# Alimentations.net
KiCad netlist of a schematic drawn in Altium Designer
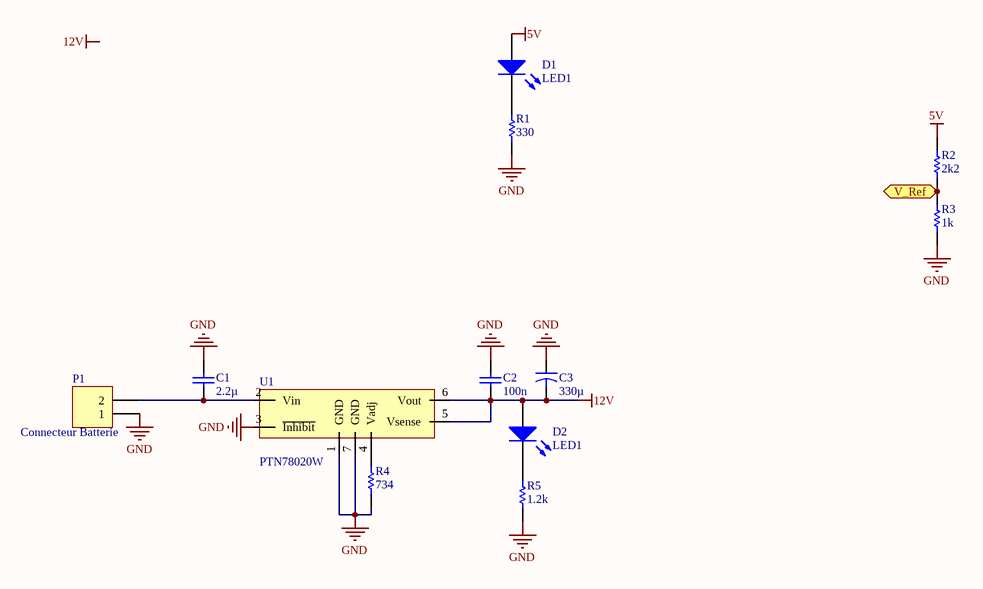
[diagram p0: Alimentations.SchDoc]

(export (version "E")
  (design (tool "Eeschema 10.0.6"))
  (components
    (comp (ref "C1")
      (value "2.2µ")
      (footprint "RAD-0.3")
      (description "Capacitor")
      (fields (field (name "Comment") "Cap") (field (name "PUBLISHER") "Altium Limited"))
      (libsource (lib "Miscellaneous Devices") (part "Cap"))
    )
    (comp (ref "C2")
      (value "100n")
      (footprint "RAD-0.3")
      (description "Capacitor")
      (fields (field (name "Comment") "Cap") (field (name "PUBLISHER") "Altium Limited"))
      (libsource (lib "Miscellaneous Devices") (part "Cap"))
    )
    (comp (ref "C3")
      (value "330µ")
      (footprint "CAPR5-4X5")
      (description "Capacitor")
      (fields (field (name "Comment") "Cap2") (field (name "PUBLISHER") "Altium Limited"))
      (libsource (lib "Miscellaneous Devices") (part "Cap2"))
    )
    (comp (ref "D1")
      (value "LED1")
      (footprint "C0805")
      (description "Typical RED GaAs LED")
      (fields (field (name "PUBLISHER") "Altium Limited"))
      (libsource (lib "Miscellaneous Devices") (part "LED1"))
    )
    (comp (ref "D2")
      (value "LED1")
      (footprint "C0805")
      (description "Typical RED GaAs LED")
      (fields (field (name "PUBLISHER") "Altium Limited"))
      (libsource (lib "Miscellaneous Devices") (part "LED1"))
    )
    (comp (ref "P1")
      (value "Connecteur Batterie")
      (footprint "HDR1X2")
      (description "Header, 2-Pin")
      (fields (field (name "PUBLISHER") "Altium Limited"))
      (libsource (lib "Miscellaneous Connectors") (part "Header 2"))
    )
    (comp (ref "R1")
      (value "330")
      (footprint "AXIAL-0.3")
      (description "Resistor")
      (fields (field (name "Comment") "Res1") (field (name "PUBLISHER") "Altium Limited"))
      (libsource (lib "Miscellaneous Devices") (part "Res1"))
    )
    (comp (ref "R2")
      (value "2k2")
      (footprint "AXIAL-0.3")
      (description "Resistor")
      (fields (field (name "Comment") "Res1") (field (name "PUBLISHER") "Altium Limited"))
      (libsource (lib "Miscellaneous Devices") (part "Res1"))
    )
    (comp (ref "R3")
      (value "1k")
      (footprint "AXIAL-0.3")
      (description "Resistor")
      (fields (field (name "Comment") "Res1") (field (name "PUBLISHER") "Altium Limited"))
      (libsource (lib "Miscellaneous Devices") (part "Res1"))
    )
    (comp (ref "R4")
      (value "734")
      (footprint "AXIAL-0.3")
      (description "Resistor")
      (fields (field (name "Comment") "Res1") (field (name "PUBLISHER") "Altium Limited"))
      (libsource (lib "Miscellaneous Devices") (part "Res1"))
    )
    (comp (ref "R5")
      (value "1.2k")
      (footprint "AXIAL-0.3")
      (description "Resistor")
      (fields (field (name "Comment") "Res1") (field (name "PUBLISHER") "Altium Limited"))
      (libsource (lib "Miscellaneous Devices") (part "Res1"))
    )
    (comp (ref "U1") (value "PTN78020W") (libsource (lib "lib_Gabriel") (part "PTN78020W")))
  )
  (nets
    (net (code "1") (name "/V_Ref") (class "Default")
      (node (ref "R2") (pin "2") (pinfunction "2_2") (pintype "passive"))
      (node (ref "R3") (pin "1") (pinfunction "1_1") (pintype "passive"))
    )
    (net (code "2") (name "5V") (class "Default")
      (node (ref "D1") (pin "1") (pinfunction "A_1") (pintype "passive"))
      (node (ref "R2") (pin "1") (pinfunction "1_1") (pintype "passive"))
    )
    (net (code "3") (name "12V") (class "Default")
      (node (ref "C2") (pin "1") (pinfunction "1_1") (pintype "passive"))
      (node (ref "C3") (pin "2") (pinfunction "2_2") (pintype "passive"))
      (node (ref "D2") (pin "1") (pinfunction "A_1") (pintype "passive"))
      (node (ref "U1") (pin "5") (pinfunction "Vsense_5") (pintype "passive"))
      (node (ref "U1") (pin "6") (pinfunction "Vout_6") (pintype "passive"))
    )
    (net (code "4") (name "GND") (class "Default")
      (node (ref "C1") (pin "2") (pinfunction "2_2") (pintype "passive"))
      (node (ref "C2") (pin "2") (pinfunction "2_2") (pintype "passive"))
      (node (ref "C3") (pin "1") (pinfunction "1_1") (pintype "passive"))
      (node (ref "P1") (pin "1") (pinfunction "1_1") (pintype "passive"))
      (node (ref "R1") (pin "2") (pinfunction "2_2") (pintype "passive"))
      (node (ref "R3") (pin "2") (pinfunction "2_2") (pintype "passive"))
      (node (ref "R4") (pin "1") (pinfunction "1_1") (pintype "passive"))
      (node (ref "R5") (pin "2") (pinfunction "2_2") (pintype "passive"))
      (node (ref "U1") (pin "1") (pinfunction "GND_1") (pintype "passive"))
      (node (ref "U1") (pin "3") (pinfunction "Inhibit_3") (pintype "passive"))
      (node (ref "U1") (pin "7") (pinfunction "GND_7") (pintype "passive"))
    )
    (net (code "5") (name "Net-(D1-K)") (class "Default")
      (node (ref "D1") (pin "2") (pinfunction "K_2") (pintype "passive"))
      (node (ref "R1") (pin "1") (pinfunction "1_1") (pintype "passive"))
    )
    (net (code "6") (name "Net-(D2-K)") (class "Default")
      (node (ref "D2") (pin "2") (pinfunction "K_2") (pintype "passive"))
      (node (ref "R5") (pin "1") (pinfunction "1_1") (pintype "passive"))
    )
    (net (code "7") (name "Net-(U1-Vadj)") (class "Default")
      (node (ref "R4") (pin "2") (pinfunction "2_2") (pintype "passive"))
      (node (ref "U1") (pin "4") (pinfunction "Vadj_4") (pintype "passive"))
    )
    (net (code "8") (name "Net-(U1-Vin)") (class "Default")
      (node (ref "C1") (pin "1") (pinfunction "1_1") (pintype "passive"))
      (node (ref "P1") (pin "2") (pinfunction "2_2") (pintype "passive"))
      (node (ref "U1") (pin "2") (pinfunction "Vin_2") (pintype "passive"))
    )
  )
)
